# Beam_Amp.net
KiCad netlist of a schematic drawn in Altium Designer
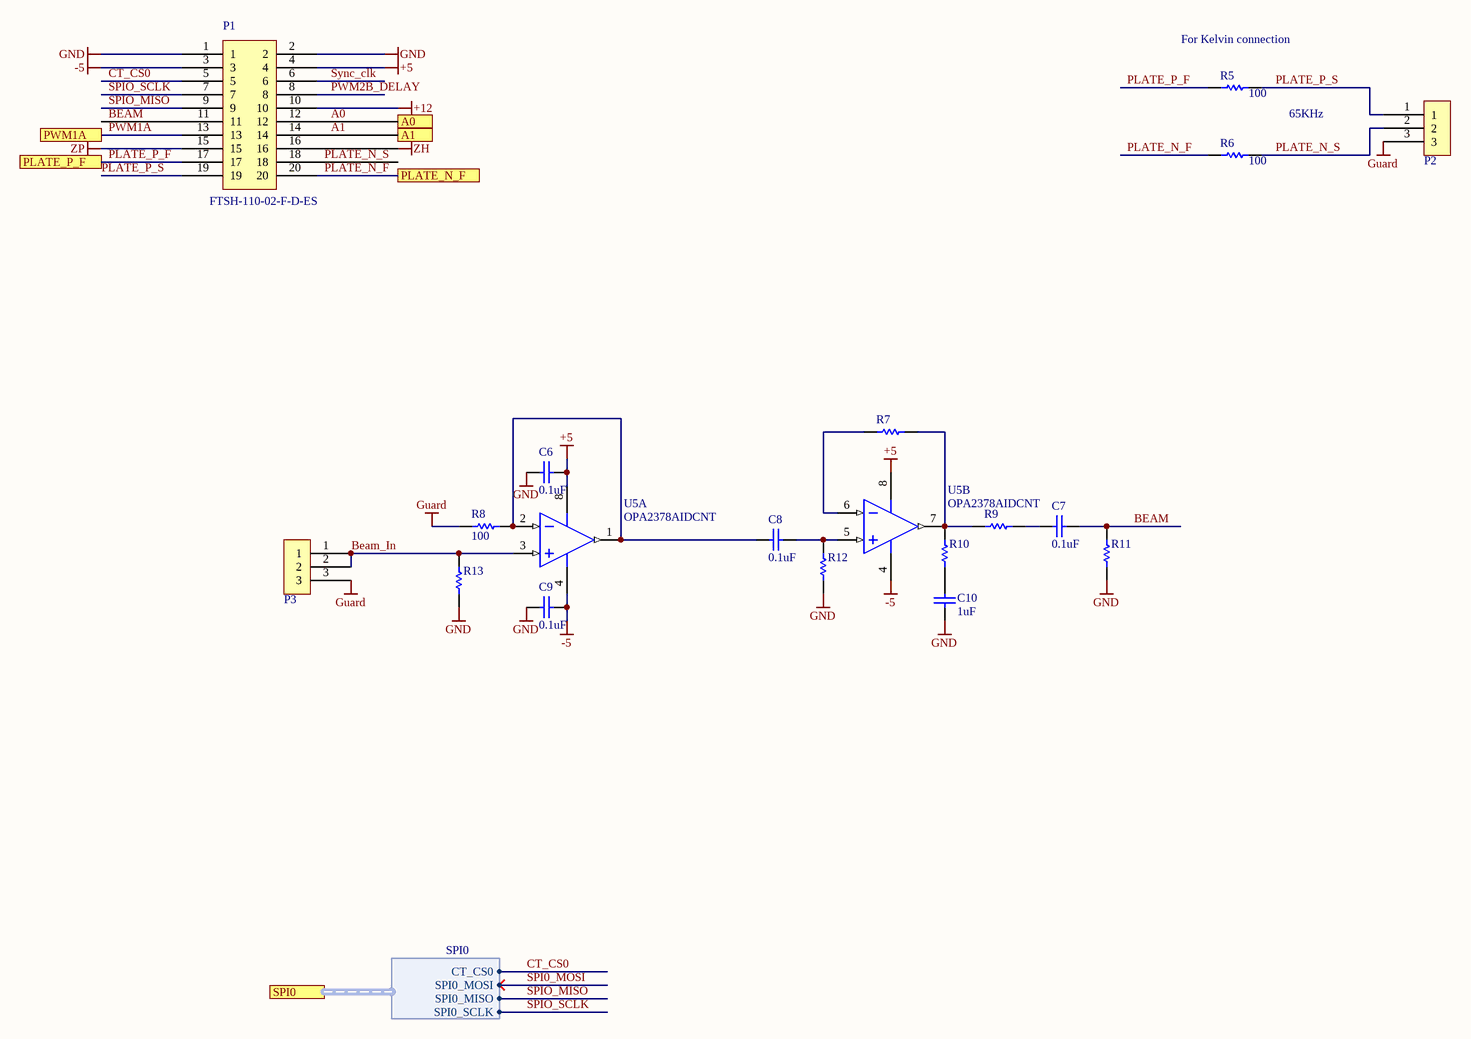
[diagram p0: Beam_Amp.SchDoc]

(export (version "E")
  (design (tool "Eeschema 10.0.6"))
  (components
    (comp (ref "C6")
      (value "0.1uF")
      (footprint "CAPC0402(1005)60_L")
      (description "CAP CER 0.1UF 10V X7R 0402")
      (fields
        (field (name "MANUFACTURER") "Murata Electronics North America")
        (field (name "MANUFACTURER PART NUMBER") "GRM155R71A104KA01D")
      )
      (libsource (lib "Altium Content Vault") (part "CMP-1034-00252-1"))
    )
    (comp (ref "C7")
      (value "0.1uF")
      (footprint "CAPC0402(1005)60_L")
      (description "CAP CER 0.1UF 10V X7R 0402")
      (fields
        (field (name "MANUFACTURER") "Murata Electronics North America")
        (field (name "MANUFACTURER PART NUMBER") "GRM155R71A104KA01D")
      )
      (libsource (lib "Altium Content Vault") (part "CMP-1034-00252-1"))
    )
    (comp (ref "C8")
      (value "0.1uF")
      (footprint "CAPC0402(1005)60_L")
      (description "CAP CER 0.1UF 10V X7R 0402")
      (fields
        (field (name "MANUFACTURER") "Murata Electronics North America")
        (field (name "MANUFACTURER PART NUMBER") "GRM155R71A104KA01D")
      )
      (libsource (lib "Altium Content Vault") (part "CMP-1034-00252-1"))
    )
    (comp (ref "C9")
      (value "0.1uF")
      (footprint "CAPC0402(1005)60_L")
      (description "CAP CER 0.1UF 10V X7R 0402")
      (fields
        (field (name "MANUFACTURER") "Murata Electronics North America")
        (field (name "MANUFACTURER PART NUMBER") "GRM155R71A104KA01D")
      )
      (libsource (lib "Altium Content Vault") (part "CMP-1034-00252-1"))
    )
    (comp (ref "C10")
      (value "1uF")
      (footprint "CAPC0402(1005)60_L")
      (description "CAP CER 0.1UF 10V X7R 0402")
      (fields
        (field (name "MANUFACTURER") "Murata Electronics North America")
        (field (name "MANUFACTURER PART NUMBER") "GRM155R71A104KA01D")
      )
      (libsource (lib "Altium Content Vault") (part "CMP-1034-00252-1"))
    )
    (comp (ref "P1")
      (value "FTSH-110-02-F-D-ES")
      (footprint "FTSH-110-02-F-D-ES")
      (libsource (lib "ZLS_Schematic_lib") (part "FTSH-110-02-F-D-ES"))
    )
    (comp (ref "P2")
      (value "Triax_Conn")
      (footprint "Triax_Conn")
      (libsource (lib "ZLS_Schematic_lib") (part "Triax_Conn"))
    )
    (comp (ref "P3") (value "Triax_Conn") (footprint "Triax_Conn") (libsource (lib "") (part "Triax_Conn_1")))
    (comp (ref "R5")
      (value "100")
      (footprint "RESC0805(2012)_L")
      (description "RES SMD 100 OHM JUMPER 1/8W 0805")
      (libsource (lib "Altium Content Vault") (part "CMP-1013-00215-1"))
    )
    (comp (ref "R6")
      (value "100")
      (footprint "RESC0805(2012)_L")
      (description "RES SMD 100 OHM JUMPER 1/8W 0805")
      (libsource (lib "Altium Content Vault") (part "CMP-1013-00215-1"))
    )
    (comp (ref "R7")
      (value "~")
      (footprint "RESC0402(1005)_M")
      (libsource (lib "Altium Content Vault") (part "CMP-1011-00463-1"))
    )
    (comp (ref "R8")
      (value "100")
      (footprint "RESC0402(1005)_M")
      (libsource (lib "Altium Content Vault") (part "CMP-1011-00463-1"))
    )
    (comp (ref "R9")
      (value "~")
      (footprint "RESC0402(1005)_M")
      (libsource (lib "Altium Content Vault") (part "CMP-1011-00463-1"))
    )
    (comp (ref "R10")
      (value "~")
      (footprint "RESC0402(1005)_M")
      (libsource (lib "Altium Content Vault") (part "CMP-1011-00463-1"))
    )
    (comp (ref "R11")
      (value "~")
      (footprint "RESC0402(1005)_M")
      (libsource (lib "Altium Content Vault") (part "CMP-1011-00463-1"))
    )
    (comp (ref "R12")
      (value "~")
      (footprint "RESC0402(1005)_M")
      (libsource (lib "Altium Content Vault") (part "CMP-1011-00463-1"))
    )
    (comp (ref "R13")
      (value "~")
      (footprint "RESC0402(1005)_M")
      (libsource (lib "Altium Content Vault") (part "CMP-1011-00463-1"))
    )
    (comp (ref "U5")
      (value "OPA2378AIDCNT")
      (footprint "DCN0008A_M")
      (fields (field (name "MANUFACTURER") "Texas Instruments"))
      (libsource (lib "Altium Content Vault") (part "TI-OPA-8_2"))
    )
  )
  (nets
    (net (code "2") (name "+5") (class "Default")
      (node (ref "C6") (pin "2") (pinfunction "2_2") (pintype "passive"))
      (node (ref "P1") (pin "4") (pinfunction "4_4") (pintype "passive"))
      (node (ref "U5") (pin "8") (pinfunction "V+_8") (pintype "power_in"))
    )
    (net (code "3") (name "+12") (class "Default")
      (node (ref "P1") (pin "10") (pinfunction "10_10") (pintype "passive"))
    )
    (net (code "4") (name "-5") (class "Default")
      (node (ref "C9") (pin "2") (pinfunction "2_2") (pintype "passive"))
      (node (ref "P1") (pin "3") (pinfunction "3_3") (pintype "passive"))
      (node (ref "U5") (pin "4") (pinfunction "V-_4") (pintype "power_in"))
    )
    (net (code "5") (name "/A0") (class "Default")
      (node (ref "P1") (pin "12") (pinfunction "12_12") (pintype "passive"))
    )
    (net (code "6") (name "/A1") (class "Default")
      (node (ref "P1") (pin "14") (pinfunction "14_14") (pintype "passive"))
    )
    (net (code "7") (name "/BEAM") (class "Default")
      (node (ref "C7") (pin "2") (pinfunction "2_2") (pintype "passive"))
      (node (ref "P1") (pin "11") (pinfunction "11_11") (pintype "passive"))
      (node (ref "R11") (pin "1") (pinfunction "1_1") (pintype "passive"))
    )
    (net (code "8") (name "/Beam_In") (class "Default")
      (node (ref "P3") (pin "1") (pinfunction "1_1") (pintype "passive"))
      (node (ref "P3") (pin "2") (pinfunction "2_2") (pintype "passive"))
      (node (ref "R13") (pin "2") (pinfunction "2_2") (pintype "passive"))
      (node (ref "U5") (pin "3") (pinfunction "IN_A+_3") (pintype "input"))
    )
    (net (code "9") (name "/CT_CS0") (class "Default")
      (node (ref "P1") (pin "5") (pinfunction "5_5") (pintype "passive"))
    )
    (net (code "10") (name "/PLATE_N_F") (class "Default")
      (node (ref "P1") (pin "20") (pinfunction "20_20") (pintype "passive"))
      (node (ref "R6") (pin "2") (pinfunction "2_2") (pintype "passive"))
    )
    (net (code "11") (name "/PLATE_N_S") (class "Default")
      (node (ref "P1") (pin "18") (pinfunction "18_18") (pintype "passive"))
      (node (ref "P2") (pin "2") (pinfunction "2_2") (pintype "passive"))
      (node (ref "R6") (pin "1") (pinfunction "1_1") (pintype "passive"))
    )
    (net (code "12") (name "/PLATE_P_F") (class "Default")
      (node (ref "P1") (pin "17") (pinfunction "17_17") (pintype "passive"))
      (node (ref "R5") (pin "2") (pinfunction "2_2") (pintype "passive"))
    )
    (net (code "13") (name "/PLATE_P_S") (class "Default")
      (node (ref "P1") (pin "19") (pinfunction "19_19") (pintype "passive"))
      (node (ref "P2") (pin "1") (pinfunction "1_1") (pintype "passive"))
      (node (ref "R5") (pin "1") (pinfunction "1_1") (pintype "passive"))
    )
    (net (code "14") (name "/PWM1A") (class "Default")
      (node (ref "P1") (pin "13") (pinfunction "13_13") (pintype "passive"))
    )
    (net (code "15") (name "/PWM2B_DELAY") (class "Default")
      (node (ref "P1") (pin "8") (pinfunction "8_8") (pintype "passive"))
    )
    (net (code "17") (name "/SPIO_MISO") (class "Default")
      (node (ref "P1") (pin "9") (pinfunction "9_9") (pintype "passive"))
    )
    (net (code "18") (name "/SPIO_SCLK") (class "Default")
      (node (ref "P1") (pin "7") (pinfunction "7_7") (pintype "passive"))
    )
    (net (code "19") (name "/Sync_clk") (class "Default")
      (node (ref "P1") (pin "6") (pinfunction "6_6") (pintype "passive"))
    )
    (net (code "21") (name "GND") (class "Default")
      (node (ref "C10") (pin "1") (pinfunction "1_1") (pintype "passive"))
      (node (ref "C6") (pin "1") (pinfunction "1_1") (pintype "passive"))
      (node (ref "C9") (pin "1") (pinfunction "1_1") (pintype "passive"))
      (node (ref "P1") (pin "1") (pinfunction "1_1") (pintype "passive"))
      (node (ref "P1") (pin "2") (pinfunction "2_2") (pintype "passive"))
      (node (ref "R11") (pin "2") (pinfunction "2_2") (pintype "passive"))
      (node (ref "R12") (pin "2") (pinfunction "2_2") (pintype "passive"))
      (node (ref "R13") (pin "1") (pinfunction "1_1") (pintype "passive"))
    )
    (net (code "22") (name "Guard") (class "Default")
      (node (ref "P2") (pin "3") (pinfunction "3_3") (pintype "passive"))
      (node (ref "P3") (pin "3") (pinfunction "3_3") (pintype "passive"))
      (node (ref "R8") (pin "2") (pinfunction "2_2") (pintype "passive"))
    )
    (net (code "23") (name "Net-(C7-Pad1)") (class "Default")
      (node (ref "C7") (pin "1") (pinfunction "1_1") (pintype "passive"))
      (node (ref "R9") (pin "1") (pinfunction "1_1") (pintype "passive"))
    )
    (net (code "24") (name "Net-(C10-Pad2)") (class "Default")
      (node (ref "C10") (pin "2") (pinfunction "2_2") (pintype "passive"))
      (node (ref "R10") (pin "2") (pinfunction "2_2") (pintype "passive"))
    )
    (net (code "25") (name "Net-(U5A-IN_A-)") (class "Default")
      (node (ref "C8") (pin "1") (pinfunction "1_1") (pintype "passive"))
      (node (ref "R8") (pin "1") (pinfunction "1_1") (pintype "passive"))
      (node (ref "U5") (pin "1") (pinfunction "OUT_A_1") (pintype "output"))
      (node (ref "U5") (pin "2") (pinfunction "IN_A-_2") (pintype "input"))
    )
    (net (code "26") (name "Net-(U5B-IN_B+)") (class "Default")
      (node (ref "C8") (pin "2") (pinfunction "2_2") (pintype "passive"))
      (node (ref "R12") (pin "1") (pinfunction "1_1") (pintype "passive"))
      (node (ref "U5") (pin "5") (pinfunction "IN_B+_5") (pintype "input"))
    )
    (net (code "27") (name "Net-(U5B-IN_B-)") (class "Default")
      (node (ref "R7") (pin "2") (pinfunction "2_2") (pintype "passive"))
      (node (ref "U5") (pin "6") (pinfunction "IN_B-_6") (pintype "input"))
    )
    (net (code "28") (name "Net-(U5B-OUT_B)") (class "Default")
      (node (ref "R10") (pin "1") (pinfunction "1_1") (pintype "passive"))
      (node (ref "R7") (pin "1") (pinfunction "1_1") (pintype "passive"))
      (node (ref "R9") (pin "2") (pinfunction "2_2") (pintype "passive"))
      (node (ref "U5") (pin "7") (pinfunction "OUT_B_7") (pintype "output"))
    )
    (net (code "29") (name "ZH") (class "Default")
      (node (ref "P1") (pin "16") (pinfunction "16_16") (pintype "passive"))
    )
    (net (code "30") (name "ZP") (class "Default")
      (node (ref "P1") (pin "15") (pinfunction "15_15") (pintype "passive"))
    )
  )
)
